# Huitzil2.net
KiCad netlist of a schematic drawn in Altium Designer
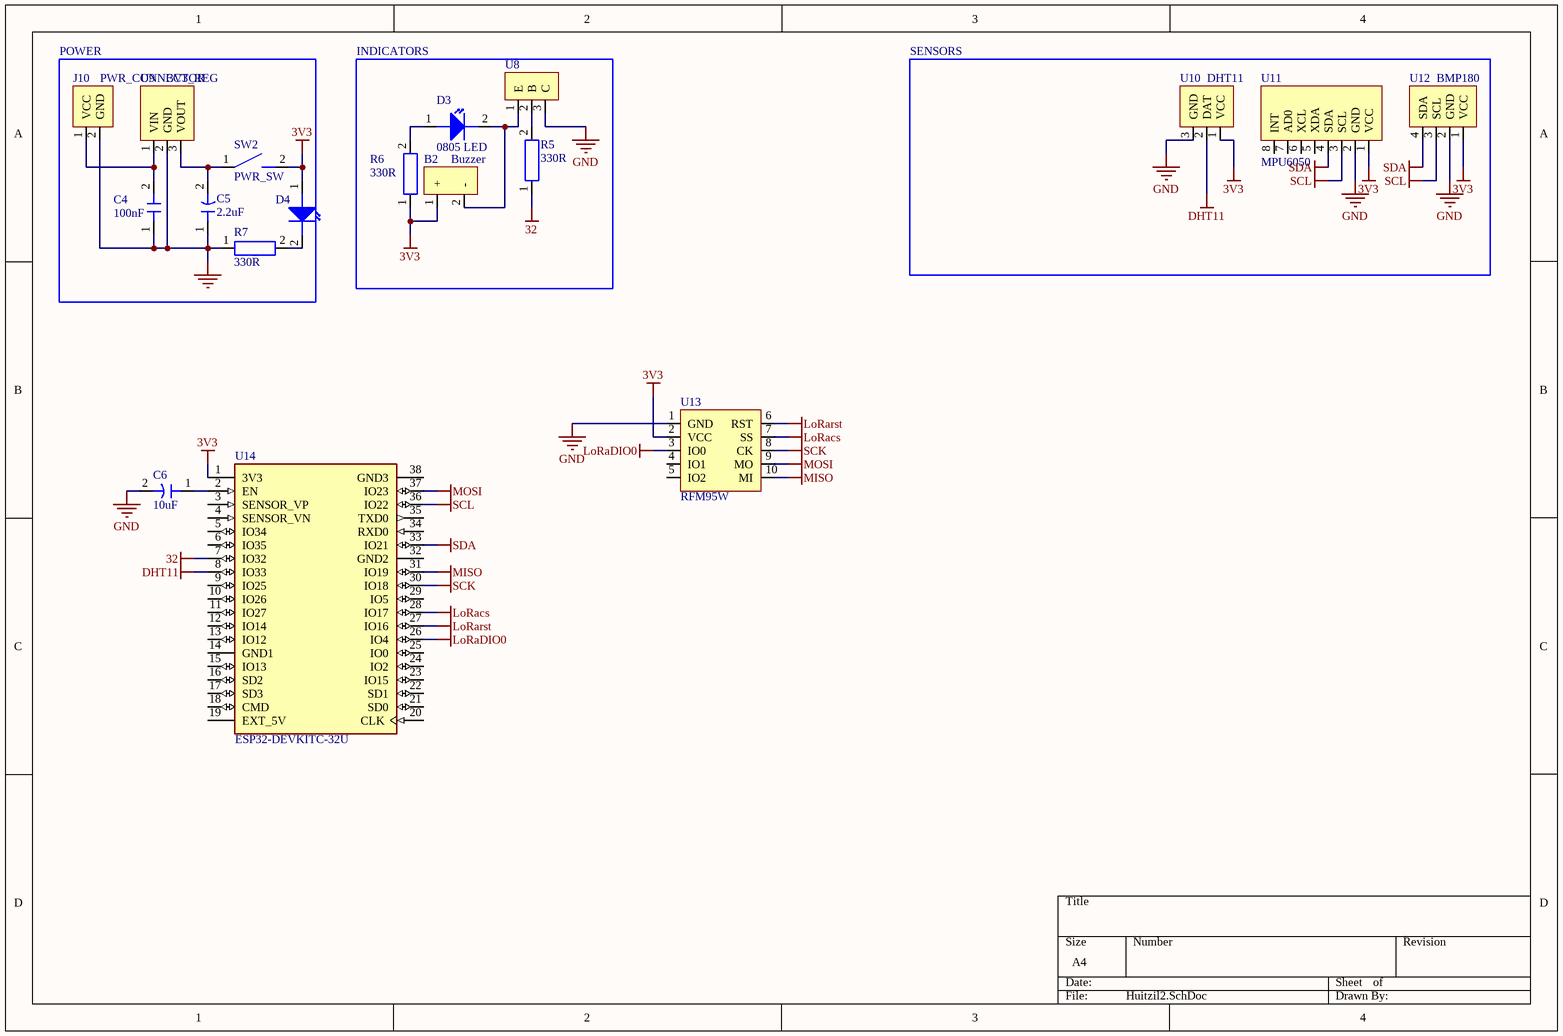
[diagram p0: Huitzil2.SchDoc]

(export (version "E")
  (design (tool "Eeschema 10.0.6"))
  (components
    (comp (ref "B2")
      (value "Buzzer")
      (footprint "BUZZER")
      (description "Active buzzer")
      (libsource (lib "CanSat1_SchLib") (part "BUZZER"))
    )
    (comp (ref "C4")
      (value "100nF")
      (footprint "CERAMIC CAP")
      (description "Ceramic through-hole capacitor")
      (libsource (lib "CanSat1_SchLib") (part "CAP"))
    )
    (comp (ref "C5")
      (value "2.2uF")
      (footprint "Electrolytic capacitor 2mm")
      (description "Throug-hole 2.2uF")
      (libsource (lib "CanSat1_SchLib") (part "E_CAP_2.2uF"))
    )
    (comp (ref "C6")
      (value "10uF")
      (footprint "Electrolytic capacitor 2mm")
      (description "Throug-hole 10uF")
      (libsource (lib "CanSat1_SchLib") (part "E_CAP_10uF"))
    )
    (comp (ref "D3")
      (value "0805 LED")
      (footprint "3mm_LED")
      (description "Through-hole LED")
      (libsource (lib "CanSat1_SchLib") (part "LED"))
    )
    (comp (ref "D4")
      (value "0805 LED")
      (footprint "3mm_LED")
      (description "Through-hole LED")
      (libsource (lib "CanSat1_SchLib") (part "LED"))
    )
    (comp (ref "J10")
      (value "PWR_CONNECTOR")
      (footprint "BATT")
      (description "THT Connector")
      (libsource (lib "CanSat1_SchLib") (part "PWR-CONN"))
    )
    (comp (ref "R5")
      (value "330R")
      (footprint "THT RESISTOR")
      (description "Through-hole resistor")
      (libsource (lib "CanSat1_SchLib") (part "Resistor"))
    )
    (comp (ref "R6")
      (value "330R")
      (footprint "THT RESISTOR")
      (description "Through-hole resistor")
      (libsource (lib "CanSat1_SchLib") (part "Resistor"))
    )
    (comp (ref "R7")
      (value "330R")
      (footprint "THT RESISTOR")
      (description "Through-hole resistor")
      (libsource (lib "CanSat1_SchLib") (part "Resistor"))
    )
    (comp (ref "SW2")
      (value "PWR_SW")
      (footprint "PWR-SW")
      (description "Mechanical through-hole switch")
      (libsource (lib "CanSat1_SchLib") (part "SWITCH"))
    )
    (comp (ref "U8")
      (value "NPN Transistor")
      (footprint "CanSat1PcbLib:2N2222A")
      (description "Through-hole NPN Transistor")
      (libsource (lib "CanSat1_SchLib") (part "2N2222"))
    )
    (comp (ref "U9")
      (value "3V3_REG")
      (footprint "LF33CV")
      (description "Through-hole 3.3V regulator")
      (libsource (lib "CanSat1_SchLib") (part "LF33CV"))
    )
    (comp (ref "U10")
      (value "DHT11")
      (footprint "DHT11")
      (description "Humidity and temperature sensor")
      (libsource (lib "CanSat1_SchLib") (part "DHT11"))
    )
    (comp (ref "U11")
      (value "MPU6050")
      (footprint "MPU6050")
      (description "6DOF IMU sensor")
      (libsource (lib "CanSat1_SchLib") (part "MPU6050"))
    )
    (comp (ref "U12")
      (value "BMP180")
      (footprint "BMP180")
      (description "Bosch Pressure Sensor")
      (libsource (lib "CanSat1_SchLib") (part "BMP180"))
    )
    (comp (ref "U13")
      (value "RFM95W")
      (footprint "Bluee LoRa")
      (description "915 MHz LoRa Transceiver")
      (libsource (lib "CanSat1_SchLib") (part "RMF95W"))
    )
    (comp (ref "U14")
      (value "ESP32-DEVKITC-32U")
      (footprint "MODULE_ESP32-DEVKITC-32U")
      (fields (field (name "MF") "Espressif Systems"))
      (libsource (lib "CanSat1_SchLib") (part "ESP32-DEVKITC-32U"))
    )
  )
  (nets
    (net (code "1") (name "3V3") (class "Default")
      (node (ref "B2") (pin "1") (pinfunction "+_1") (pintype "passive"))
      (node (ref "D4") (pin "1") (pinfunction "A_1") (pintype "passive"))
      (node (ref "R6") (pin "1") (pinfunction "1_1") (pintype "passive"))
      (node (ref "SW2") (pin "2") (pinfunction "+_2") (pintype "passive"))
      (node (ref "U10") (pin "1") (pinfunction "VCC_1") (pintype "passive"))
      (node (ref "U11") (pin "1") (pinfunction "VCC_1") (pintype "passive"))
      (node (ref "U12") (pin "1") (pinfunction "VCC_1") (pintype "passive"))
      (node (ref "U13") (pin "2") (pinfunction "VCC_2") (pintype "passive"))
      (node (ref "U14") (pin "1") (pinfunction "3V3_1") (pintype "power_in"))
    )
    (net (code "2") (name "32") (class "Default")
      (node (ref "R5") (pin "1") (pinfunction "1_1") (pintype "passive"))
      (node (ref "U14") (pin "7") (pinfunction "IO32_7") (pintype "bidirectional"))
    )
    (net (code "3") (name "DHT11") (class "Default")
      (node (ref "U10") (pin "2") (pinfunction "DAT_2") (pintype "passive"))
      (node (ref "U14") (pin "8") (pinfunction "IO33_8") (pintype "bidirectional"))
    )
    (net (code "4") (name "GND") (class "Default")
      (node (ref "C4") (pin "1") (pinfunction "+_1") (pintype "passive"))
      (node (ref "C5") (pin "1") (pinfunction "+_1") (pintype "passive"))
      (node (ref "C6") (pin "2") (pinfunction "-_2") (pintype "passive"))
      (node (ref "J10") (pin "2") (pinfunction "GND_2") (pintype "passive"))
      (node (ref "R7") (pin "1") (pinfunction "1_1") (pintype "passive"))
      (node (ref "U10") (pin "3") (pinfunction "GND_3") (pintype "passive"))
      (node (ref "U11") (pin "2") (pinfunction "GND_2") (pintype "passive"))
      (node (ref "U12") (pin "2") (pinfunction "GND_2") (pintype "passive"))
      (node (ref "U13") (pin "1") (pinfunction "GND_1") (pintype "passive"))
      (node (ref "U8") (pin "3") (pinfunction "C_3") (pintype "passive"))
      (node (ref "U9") (pin "2") (pinfunction "GND_2") (pintype "passive"))
    )
    (net (code "5") (name "LoRaDIO0") (class "Default")
      (node (ref "U13") (pin "3") (pinfunction "IO0_3") (pintype "passive"))
      (node (ref "U14") (pin "26") (pinfunction "IO4_26") (pintype "bidirectional"))
    )
    (net (code "6") (name "LoRacs") (class "Default")
      (node (ref "U13") (pin "7") (pinfunction "SS_7") (pintype "passive"))
      (node (ref "U14") (pin "28") (pinfunction "IO17_28") (pintype "bidirectional"))
    )
    (net (code "7") (name "LoRarst") (class "Default")
      (node (ref "U13") (pin "6") (pinfunction "RST_6") (pintype "passive"))
      (node (ref "U14") (pin "27") (pinfunction "IO16_27") (pintype "bidirectional"))
    )
    (net (code "8") (name "MISO") (class "Default")
      (node (ref "U13") (pin "10") (pinfunction "MI_10") (pintype "passive"))
      (node (ref "U14") (pin "31") (pinfunction "IO19_31") (pintype "bidirectional"))
    )
    (net (code "9") (name "MOSI") (class "Default")
      (node (ref "U13") (pin "9") (pinfunction "MO_9") (pintype "passive"))
      (node (ref "U14") (pin "37") (pinfunction "IO23_37") (pintype "bidirectional"))
    )
    (net (code "10") (name "Net-(B2--)") (class "Default")
      (node (ref "B2") (pin "2") (pinfunction "-_2") (pintype "passive"))
      (node (ref "D3") (pin "2") (pinfunction "K_2") (pintype "passive"))
      (node (ref "U8") (pin "1") (pinfunction "E_1") (pintype "passive"))
    )
    (net (code "11") (name "Net-(C4--)") (class "Default")
      (node (ref "C4") (pin "2") (pinfunction "-_2") (pintype "passive"))
      (node (ref "J10") (pin "1") (pinfunction "VCC_1") (pintype "passive"))
      (node (ref "U9") (pin "1") (pinfunction "VIN_1") (pintype "passive"))
    )
    (net (code "12") (name "Net-(C5--)") (class "Default")
      (node (ref "C5") (pin "2") (pinfunction "-_2") (pintype "passive"))
      (node (ref "SW2") (pin "1") (pinfunction "+_1") (pintype "passive"))
      (node (ref "U9") (pin "3") (pinfunction "VOUT_3") (pintype "passive"))
    )
    (net (code "13") (name "Net-(C6-+)") (class "Default")
      (node (ref "C6") (pin "1") (pinfunction "+_1") (pintype "passive"))
      (node (ref "U14") (pin "2") (pinfunction "EN_2") (pintype "input"))
    )
    (net (code "14") (name "Net-(D3-A)") (class "Default")
      (node (ref "D3") (pin "1") (pinfunction "A_1") (pintype "passive"))
      (node (ref "R6") (pin "2") (pinfunction "2_2") (pintype "passive"))
    )
    (net (code "15") (name "Net-(D4-K)") (class "Default")
      (node (ref "D4") (pin "2") (pinfunction "K_2") (pintype "passive"))
      (node (ref "R7") (pin "2") (pinfunction "2_2") (pintype "passive"))
    )
    (net (code "16") (name "Net-(U8-B)") (class "Default")
      (node (ref "R5") (pin "2") (pinfunction "2_2") (pintype "passive"))
      (node (ref "U8") (pin "2") (pinfunction "B_2") (pintype "passive"))
    )
    (net (code "17") (name "SCK") (class "Default")
      (node (ref "U13") (pin "8") (pinfunction "CK_8") (pintype "passive"))
      (node (ref "U14") (pin "30") (pinfunction "IO18_30") (pintype "bidirectional"))
    )
    (net (code "18") (name "SCL") (class "Default")
      (node (ref "U11") (pin "3") (pinfunction "SCL_3") (pintype "passive"))
      (node (ref "U12") (pin "3") (pinfunction "SCL_3") (pintype "passive"))
      (node (ref "U14") (pin "36") (pinfunction "IO22_36") (pintype "bidirectional"))
    )
    (net (code "19") (name "SDA") (class "Default")
      (node (ref "U11") (pin "4") (pinfunction "SDA_4") (pintype "passive"))
      (node (ref "U12") (pin "4") (pinfunction "SDA_4") (pintype "passive"))
      (node (ref "U14") (pin "33") (pinfunction "IO21_33") (pintype "bidirectional"))
    )
    (net (code "20") (name "unconnected-(U11-AD0-Pad7)") (class "Default")
      (node (ref "U11") (pin "7") (pinfunction "AD0_7") (pintype "passive"))
    )
    (net (code "21") (name "unconnected-(U11-INT-Pad8)") (class "Default")
      (node (ref "U11") (pin "8") (pinfunction "INT_8") (pintype "passive"))
    )
    (net (code "22") (name "unconnected-(U11-XCL-Pad6)") (class "Default")
      (node (ref "U11") (pin "6") (pinfunction "XCL_6") (pintype "passive"))
    )
    (net (code "23") (name "unconnected-(U11-XDA-Pad5)") (class "Default")
      (node (ref "U11") (pin "5") (pinfunction "XDA_5") (pintype "passive"))
    )
    (net (code "24") (name "unconnected-(U13-IO1-Pad4)") (class "Default")
      (node (ref "U13") (pin "4") (pinfunction "IO1_4") (pintype "passive"))
    )
    (net (code "25") (name "unconnected-(U13-IO2-Pad5)") (class "Default")
      (node (ref "U13") (pin "5") (pinfunction "IO2_5") (pintype "passive"))
    )
    (net (code "26") (name "unconnected-(U14-CLK-Pad20)") (class "Default")
      (node (ref "U14") (pin "20") (pinfunction "CLK_20") (pintype "input"))
    )
    (net (code "27") (name "unconnected-(U14-CMD-Pad18)") (class "Default")
      (node (ref "U14") (pin "18") (pinfunction "CMD_18") (pintype "bidirectional"))
    )
    (net (code "28") (name "unconnected-(U14-EXT_5V-Pad19)") (class "Default")
      (node (ref "U14") (pin "19") (pinfunction "EXT_5V_19") (pintype "power_in"))
    )
    (net (code "29") (name "unconnected-(U14-GND1-Pad14)") (class "Default")
      (node (ref "U14") (pin "14") (pinfunction "GND1_14") (pintype "power_in"))
    )
    (net (code "30") (name "unconnected-(U14-GND2-Pad32)") (class "Default")
      (node (ref "U14") (pin "32") (pinfunction "GND2_32") (pintype "power_in"))
    )
    (net (code "31") (name "unconnected-(U14-GND3-Pad38)") (class "Default")
      (node (ref "U14") (pin "38") (pinfunction "GND3_38") (pintype "power_in"))
    )
    (net (code "32") (name "unconnected-(U14-IO0-Pad25)") (class "Default")
      (node (ref "U14") (pin "25") (pinfunction "IO0_25") (pintype "bidirectional"))
    )
    (net (code "33") (name "unconnected-(U14-IO2-Pad24)") (class "Default")
      (node (ref "U14") (pin "24") (pinfunction "IO2_24") (pintype "bidirectional"))
    )
    (net (code "34") (name "unconnected-(U14-IO5-Pad29)") (class "Default")
      (node (ref "U14") (pin "29") (pinfunction "IO5_29") (pintype "bidirectional"))
    )
    (net (code "35") (name "unconnected-(U14-IO12-Pad13)") (class "Default")
      (node (ref "U14") (pin "13") (pinfunction "IO12_13") (pintype "bidirectional"))
    )
    (net (code "36") (name "unconnected-(U14-IO13-Pad15)") (class "Default")
      (node (ref "U14") (pin "15") (pinfunction "IO13_15") (pintype "bidirectional"))
    )
    (net (code "37") (name "unconnected-(U14-IO14-Pad12)") (class "Default")
      (node (ref "U14") (pin "12") (pinfunction "IO14_12") (pintype "bidirectional"))
    )
    (net (code "38") (name "unconnected-(U14-IO15-Pad23)") (class "Default")
      (node (ref "U14") (pin "23") (pinfunction "IO15_23") (pintype "bidirectional"))
    )
    (net (code "39") (name "unconnected-(U14-IO25-Pad9)") (class "Default")
      (node (ref "U14") (pin "9") (pinfunction "IO25_9") (pintype "bidirectional"))
    )
    (net (code "40") (name "unconnected-(U14-IO26-Pad10)") (class "Default")
      (node (ref "U14") (pin "10") (pinfunction "IO26_10") (pintype "bidirectional"))
    )
    (net (code "41") (name "unconnected-(U14-IO27-Pad11)") (class "Default")
      (node (ref "U14") (pin "11") (pinfunction "IO27_11") (pintype "bidirectional"))
    )
    (net (code "42") (name "unconnected-(U14-IO34-Pad5)") (class "Default")
      (node (ref "U14") (pin "5") (pinfunction "IO34_5") (pintype "bidirectional"))
    )
    (net (code "43") (name "unconnected-(U14-IO35-Pad6)") (class "Default")
      (node (ref "U14") (pin "6") (pinfunction "IO35_6") (pintype "bidirectional"))
    )
    (net (code "44") (name "unconnected-(U14-RXD0-Pad34)") (class "Default")
      (node (ref "U14") (pin "34") (pinfunction "RXD0_34") (pintype "input"))
    )
    (net (code "45") (name "unconnected-(U14-SD0-Pad21)") (class "Default")
      (node (ref "U14") (pin "21") (pinfunction "SD0_21") (pintype "bidirectional"))
    )
    (net (code "46") (name "unconnected-(U14-SD1-Pad22)") (class "Default")
      (node (ref "U14") (pin "22") (pinfunction "SD1_22") (pintype "bidirectional"))
    )
    (net (code "47") (name "unconnected-(U14-SD2-Pad16)") (class "Default")
      (node (ref "U14") (pin "16") (pinfunction "SD2_16") (pintype "bidirectional"))
    )
    (net (code "48") (name "unconnected-(U14-SD3-Pad17)") (class "Default")
      (node (ref "U14") (pin "17") (pinfunction "SD3_17") (pintype "bidirectional"))
    )
    (net (code "49") (name "unconnected-(U14-SENSOR_VN-Pad4)") (class "Default")
      (node (ref "U14") (pin "4") (pinfunction "SENSOR_VN_4") (pintype "input"))
    )
    (net (code "50") (name "unconnected-(U14-SENSOR_VP-Pad3)") (class "Default")
      (node (ref "U14") (pin "3") (pinfunction "SENSOR_VP_3") (pintype "input"))
    )
    (net (code "51") (name "unconnected-(U14-TXD0-Pad35)") (class "Default")
      (node (ref "U14") (pin "35") (pinfunction "TXD0_35") (pintype "output"))
    )
  )
)
